# Adafruit_BMP280_STEMMA_QT.net
KiCad netlist of a schematic drawn in EAGLE
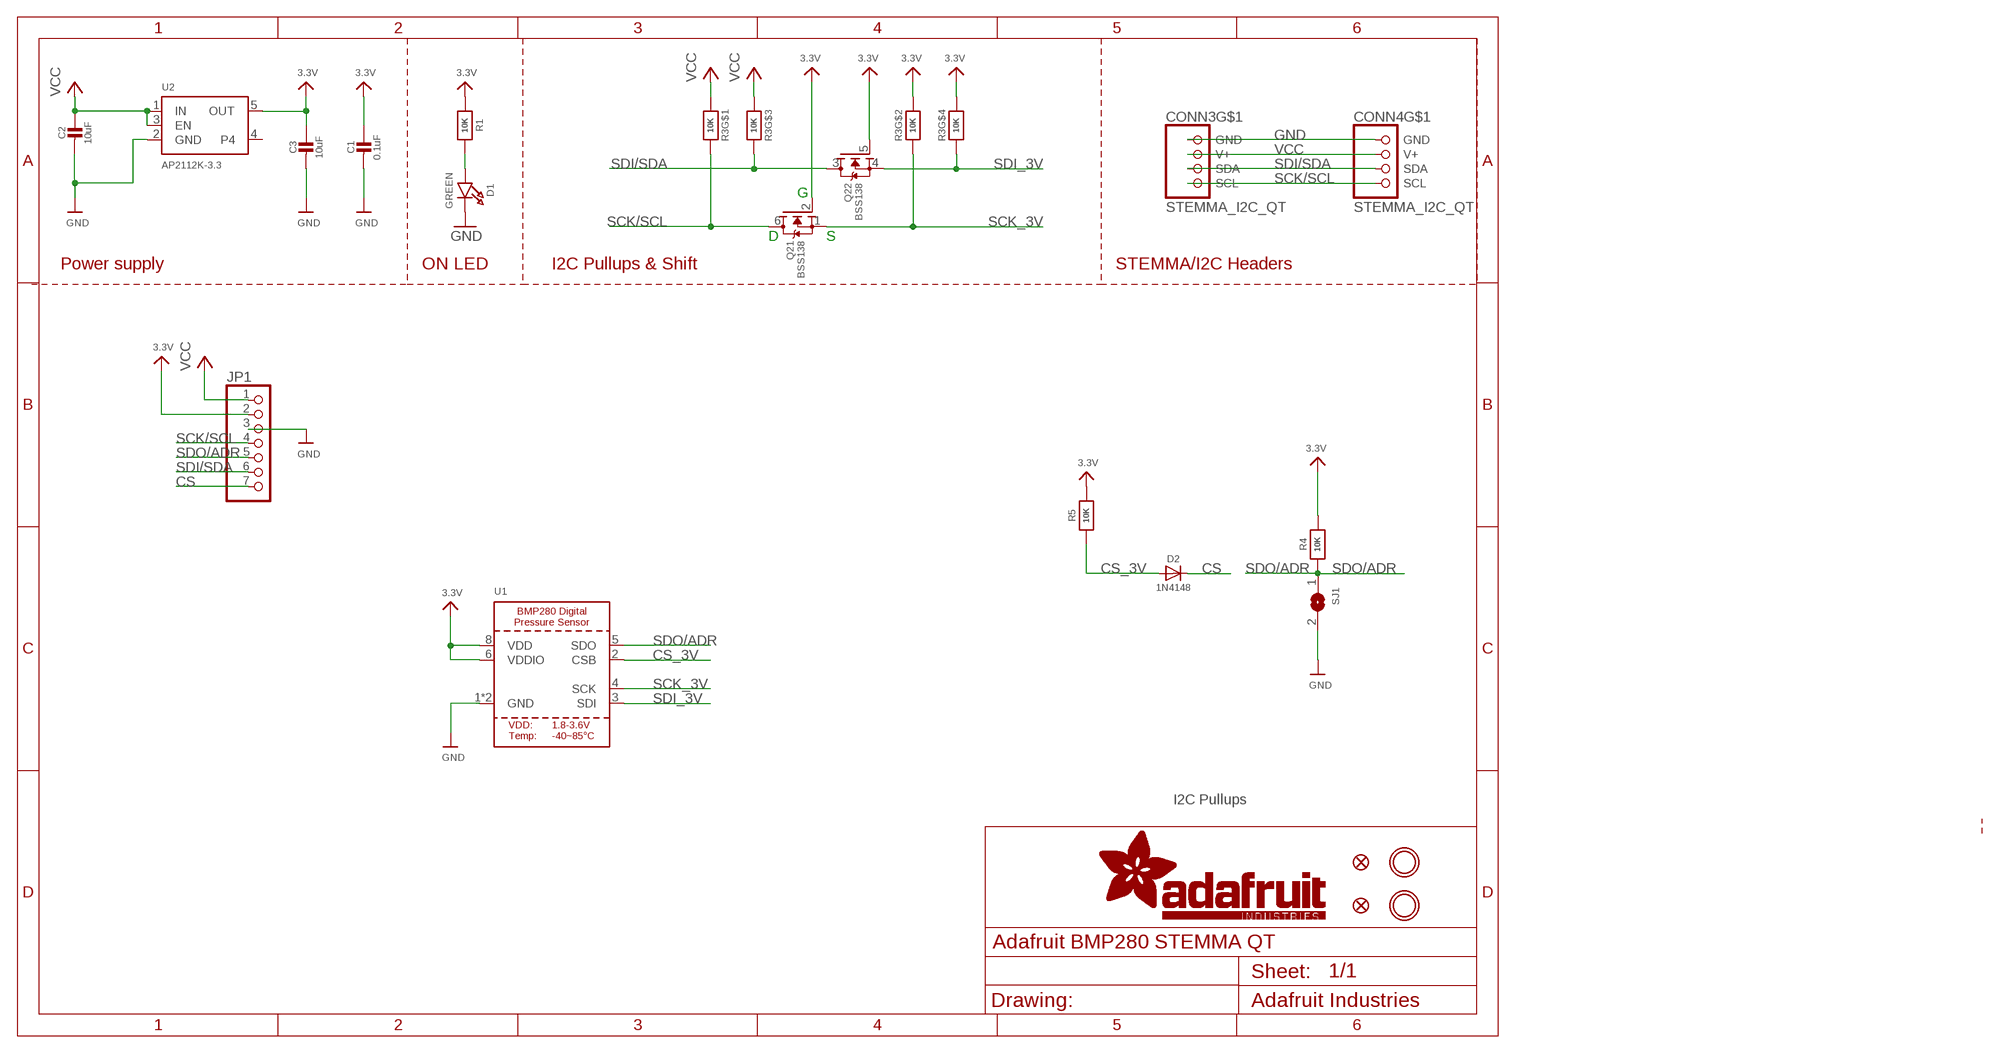
[diagram p0: schematic, sheet 1]

(export (version "E")
  (design (tool "Eeschema 10.0.6"))
  (components
    (comp (ref "C1")
      (value "0.1uF")
      (footprint "eagle-import:0603-NO")
      (libsource (lib "eagle-import") (part "CAP_CERAMIC0603_NO"))
    )
    (comp (ref "C2")
      (value "10uF")
      (footprint "eagle-import:0805-NO")
      (libsource (lib "eagle-import") (part "CAP_CERAMIC0805-NOOUTLINE"))
    )
    (comp (ref "C3")
      (value "10uF")
      (footprint "eagle-import:0805-NO")
      (libsource (lib "eagle-import") (part "CAP_CERAMIC0805-NOOUTLINE"))
    )
    (comp (ref "CONN3")
      (value "STEMMA_I2C_QT")
      (footprint "eagle-import:JST_SH4")
      (libsource (lib "eagle-import") (part "STEMMA_I2C_QT"))
    )
    (comp (ref "CONN4")
      (value "STEMMA_I2C_QT")
      (footprint "eagle-import:JST_SH4")
      (libsource (lib "eagle-import") (part "STEMMA_I2C_QT"))
    )
    (comp (ref "D1")
      (value "GREEN")
      (footprint "eagle-import:CHIPLED_0603_NOOUTLINE")
      (libsource (lib "eagle-import") (part "LED0603_NOOUTLINE"))
    )
    (comp (ref "D2")
      (value "1N4148")
      (footprint "eagle-import:SOD-323")
      (libsource (lib "eagle-import") (part "DIODESOD-323"))
    )
    (comp (ref "FID3")
      (value "FIDUCIAL_1MM")
      (footprint "eagle-import:FIDUCIAL_1MM")
      (libsource (lib "eagle-import") (part "FIDUCIAL_1MM"))
    )
    (comp (ref "FID4")
      (value "FIDUCIAL_1MM")
      (footprint "eagle-import:FIDUCIAL_1MM")
      (libsource (lib "eagle-import") (part "FIDUCIAL_1MM"))
    )
    (comp (ref "JP1")
      (value "HEADER-1X770MIL")
      (footprint "eagle-import:1X07_ROUND_70")
      (libsource (lib "eagle-import") (part "HEADER-1X770MIL"))
    )
    (comp (ref "Q2")
      (value "BSS138")
      (footprint "eagle-import:SOT363")
      (libsource (lib "eagle-import") (part "MOSFET-N_DUAL"))
    )
    (comp (ref "R1")
      (value "10K")
      (footprint "eagle-import:0603-NO")
      (libsource (lib "eagle-import") (part "RESISTOR_0603_NOOUT"))
    )
    (comp (ref "R3")
      (value "10K")
      (footprint "eagle-import:RESPACK_4X0603")
      (libsource (lib "eagle-import") (part "RESISTOR_4PACK"))
    )
    (comp (ref "R4")
      (value "10K")
      (footprint "eagle-import:0603-NO")
      (libsource (lib "eagle-import") (part "RESISTOR_0603_NOOUT"))
    )
    (comp (ref "R5")
      (value "10K")
      (footprint "eagle-import:0603-NO")
      (libsource (lib "eagle-import") (part "RESISTOR_0603_NOOUT"))
    )
    (comp (ref "SJ1")
      (value "SOLDERJUMPER")
      (footprint "eagle-import:SOLDERJUMPER_ARROW_NOPASTE")
      (libsource (lib "eagle-import") (part "SOLDERJUMPER"))
    )
    (comp (ref "U$1")
      (value "MOUNTINGHOLE2.5")
      (footprint "eagle-import:MOUNTINGHOLE_2.5_PLATED")
      (libsource (lib "eagle-import") (part "MOUNTINGHOLE2.5"))
    )
    (comp (ref "U$17")
      (value "MOUNTINGHOLE2.5")
      (footprint "eagle-import:MOUNTINGHOLE_2.5_PLATED")
      (libsource (lib "eagle-import") (part "MOUNTINGHOLE2.5"))
    )
    (comp (ref "U1")
      (value "BMP280_COMBO")
      (footprint "eagle-import:BMX280_COMBO")
      (libsource (lib "eagle-import") (part "BMP280_COMBO"))
    )
    (comp (ref "U2")
      (value "AP2112K-3.3")
      (footprint "eagle-import:SOT23-5")
      (libsource (lib "eagle-import") (part "VREG_SOT23-5"))
    )
  )
  (nets
    (net (code "1") (name "/CS") (class "Default")
      (node (ref "D2") (pin "C") (pinfunction "C_C") (pintype "passive"))
      (node (ref "JP1") (pin "7") (pinfunction "7_7") (pintype "passive"))
    )
    (net (code "2") (name "/CS_3V") (class "Default")
      (node (ref "D2") (pin "A") (pinfunction "A_A") (pintype "passive"))
      (node (ref "R5") (pin "1") (pinfunction "1_1") (pintype "passive"))
      (node (ref "U1") (pin "2") (pinfunction "CSB_2") (pintype "input"))
    )
    (net (code "3") (name "/SCK_3V") (class "Default")
      (node (ref "Q2") (pin "1") (pinfunction "S_1") (pintype "bidirectional"))
      (node (ref "R3") (pin "7") (pinfunction "2_7") (pintype "passive"))
      (node (ref "U1") (pin "4") (pinfunction "SCK_4") (pintype "input"))
    )
    (net (code "4") (name "/SCK{slash}SCL") (class "Default")
      (node (ref "CONN3") (pin "4") (pinfunction "SCL_4") (pintype "passive"))
      (node (ref "CONN4") (pin "4") (pinfunction "SCL_4") (pintype "passive"))
      (node (ref "JP1") (pin "4") (pinfunction "4_4") (pintype "passive"))
      (node (ref "Q2") (pin "6") (pinfunction "D_6") (pintype "bidirectional"))
      (node (ref "R3") (pin "8") (pinfunction "2_8") (pintype "passive"))
    )
    (net (code "5") (name "/SDI_3V") (class "Default")
      (node (ref "Q2") (pin "4") (pinfunction "S_4") (pintype "bidirectional"))
      (node (ref "R3") (pin "5") (pinfunction "2_5") (pintype "passive"))
      (node (ref "U1") (pin "3") (pinfunction "SDI_3") (pintype "input"))
    )
    (net (code "6") (name "/SDI{slash}SDA") (class "Default")
      (node (ref "CONN3") (pin "3") (pinfunction "SDA_3") (pintype "passive"))
      (node (ref "CONN4") (pin "3") (pinfunction "SDA_3") (pintype "passive"))
      (node (ref "JP1") (pin "6") (pinfunction "6_6") (pintype "passive"))
      (node (ref "Q2") (pin "3") (pinfunction "D_3") (pintype "bidirectional"))
      (node (ref "R3") (pin "6") (pinfunction "2_6") (pintype "passive"))
    )
    (net (code "7") (name "/SDO{slash}ADR") (class "Default")
      (node (ref "JP1") (pin "5") (pinfunction "5_5") (pintype "passive"))
      (node (ref "R4") (pin "1") (pinfunction "1_1") (pintype "passive"))
      (node (ref "SJ1") (pin "1") (pinfunction "1_1") (pintype "passive"))
      (node (ref "U1") (pin "5") (pinfunction "SDO_5") (pintype "output"))
    )
    (net (code "8") (name "3.3V") (class "Default")
      (node (ref "C1") (pin "1") (pinfunction "1_1") (pintype "passive"))
      (node (ref "C3") (pin "1") (pinfunction "1_1") (pintype "passive"))
      (node (ref "JP1") (pin "2") (pinfunction "2_2") (pintype "passive"))
      (node (ref "Q2") (pin "2") (pinfunction "G_2") (pintype "bidirectional"))
      (node (ref "Q2") (pin "5") (pinfunction "G_5") (pintype "bidirectional"))
      (node (ref "R1") (pin "1") (pinfunction "1_1") (pintype "passive"))
      (node (ref "R3") (pin "2") (pinfunction "1_2") (pintype "passive"))
      (node (ref "R3") (pin "4") (pinfunction "1_4") (pintype "passive"))
      (node (ref "R4") (pin "2") (pinfunction "2_2") (pintype "passive"))
      (node (ref "R5") (pin "2") (pinfunction "2_2") (pintype "passive"))
      (node (ref "U1") (pin "6") (pinfunction "VDDIO_6") (pintype "power_in"))
      (node (ref "U1") (pin "8") (pinfunction "VDD_8") (pintype "power_in"))
      (node (ref "U2") (pin "5") (pinfunction "OUT_5") (pintype "power_in"))
    )
    (net (code "9") (name "GND") (class "Default")
      (node (ref "C1") (pin "2") (pinfunction "2_2") (pintype "passive"))
      (node (ref "C2") (pin "2") (pinfunction "2_2") (pintype "passive"))
      (node (ref "C3") (pin "2") (pinfunction "2_2") (pintype "passive"))
      (node (ref "CONN3") (pin "1") (pinfunction "GND_1") (pintype "passive"))
      (node (ref "CONN4") (pin "1") (pinfunction "GND_1") (pintype "passive"))
      (node (ref "D1") (pin "C") (pinfunction "C_C") (pintype "passive"))
      (node (ref "JP1") (pin "3") (pinfunction "3_3") (pintype "passive"))
      (node (ref "SJ1") (pin "2") (pinfunction "2_2") (pintype "passive"))
      (node (ref "U1") (pin "1") (pinfunction "GND_1") (pintype "power_in"))
      (node (ref "U1") (pin "7") (pinfunction "GND_7") (pintype "power_in"))
      (node (ref "U2") (pin "2") (pinfunction "GND_2") (pintype "power_in"))
    )
    (net (code "10") (name "Net-(D1-PadA)") (class "Default")
      (node (ref "D1") (pin "A") (pinfunction "A_A") (pintype "passive"))
      (node (ref "R1") (pin "2") (pinfunction "2_2") (pintype "passive"))
    )
    (net (code "11") (name "VCC") (class "Default")
      (node (ref "C2") (pin "1") (pinfunction "1_1") (pintype "passive"))
      (node (ref "CONN3") (pin "2") (pinfunction "V+_2") (pintype "passive"))
      (node (ref "CONN4") (pin "2") (pinfunction "V+_2") (pintype "passive"))
      (node (ref "JP1") (pin "1") (pinfunction "1_1") (pintype "passive"))
      (node (ref "R3") (pin "1") (pinfunction "1_1") (pintype "passive"))
      (node (ref "R3") (pin "3") (pinfunction "1_3") (pintype "passive"))
      (node (ref "U2") (pin "1") (pinfunction "IN_1") (pintype "power_in"))
      (node (ref "U2") (pin "3") (pinfunction "EN_3") (pintype "input"))
    )
    (net (code "12") (name "unconnected-(U2-P4-Pad4)") (class "Default")
      (node (ref "U2") (pin "4") (pinfunction "P4_4") (pintype "bidirectional"))
    )
  )
)
